# RX.net
KiCad netlist of a schematic drawn in Altium Designer
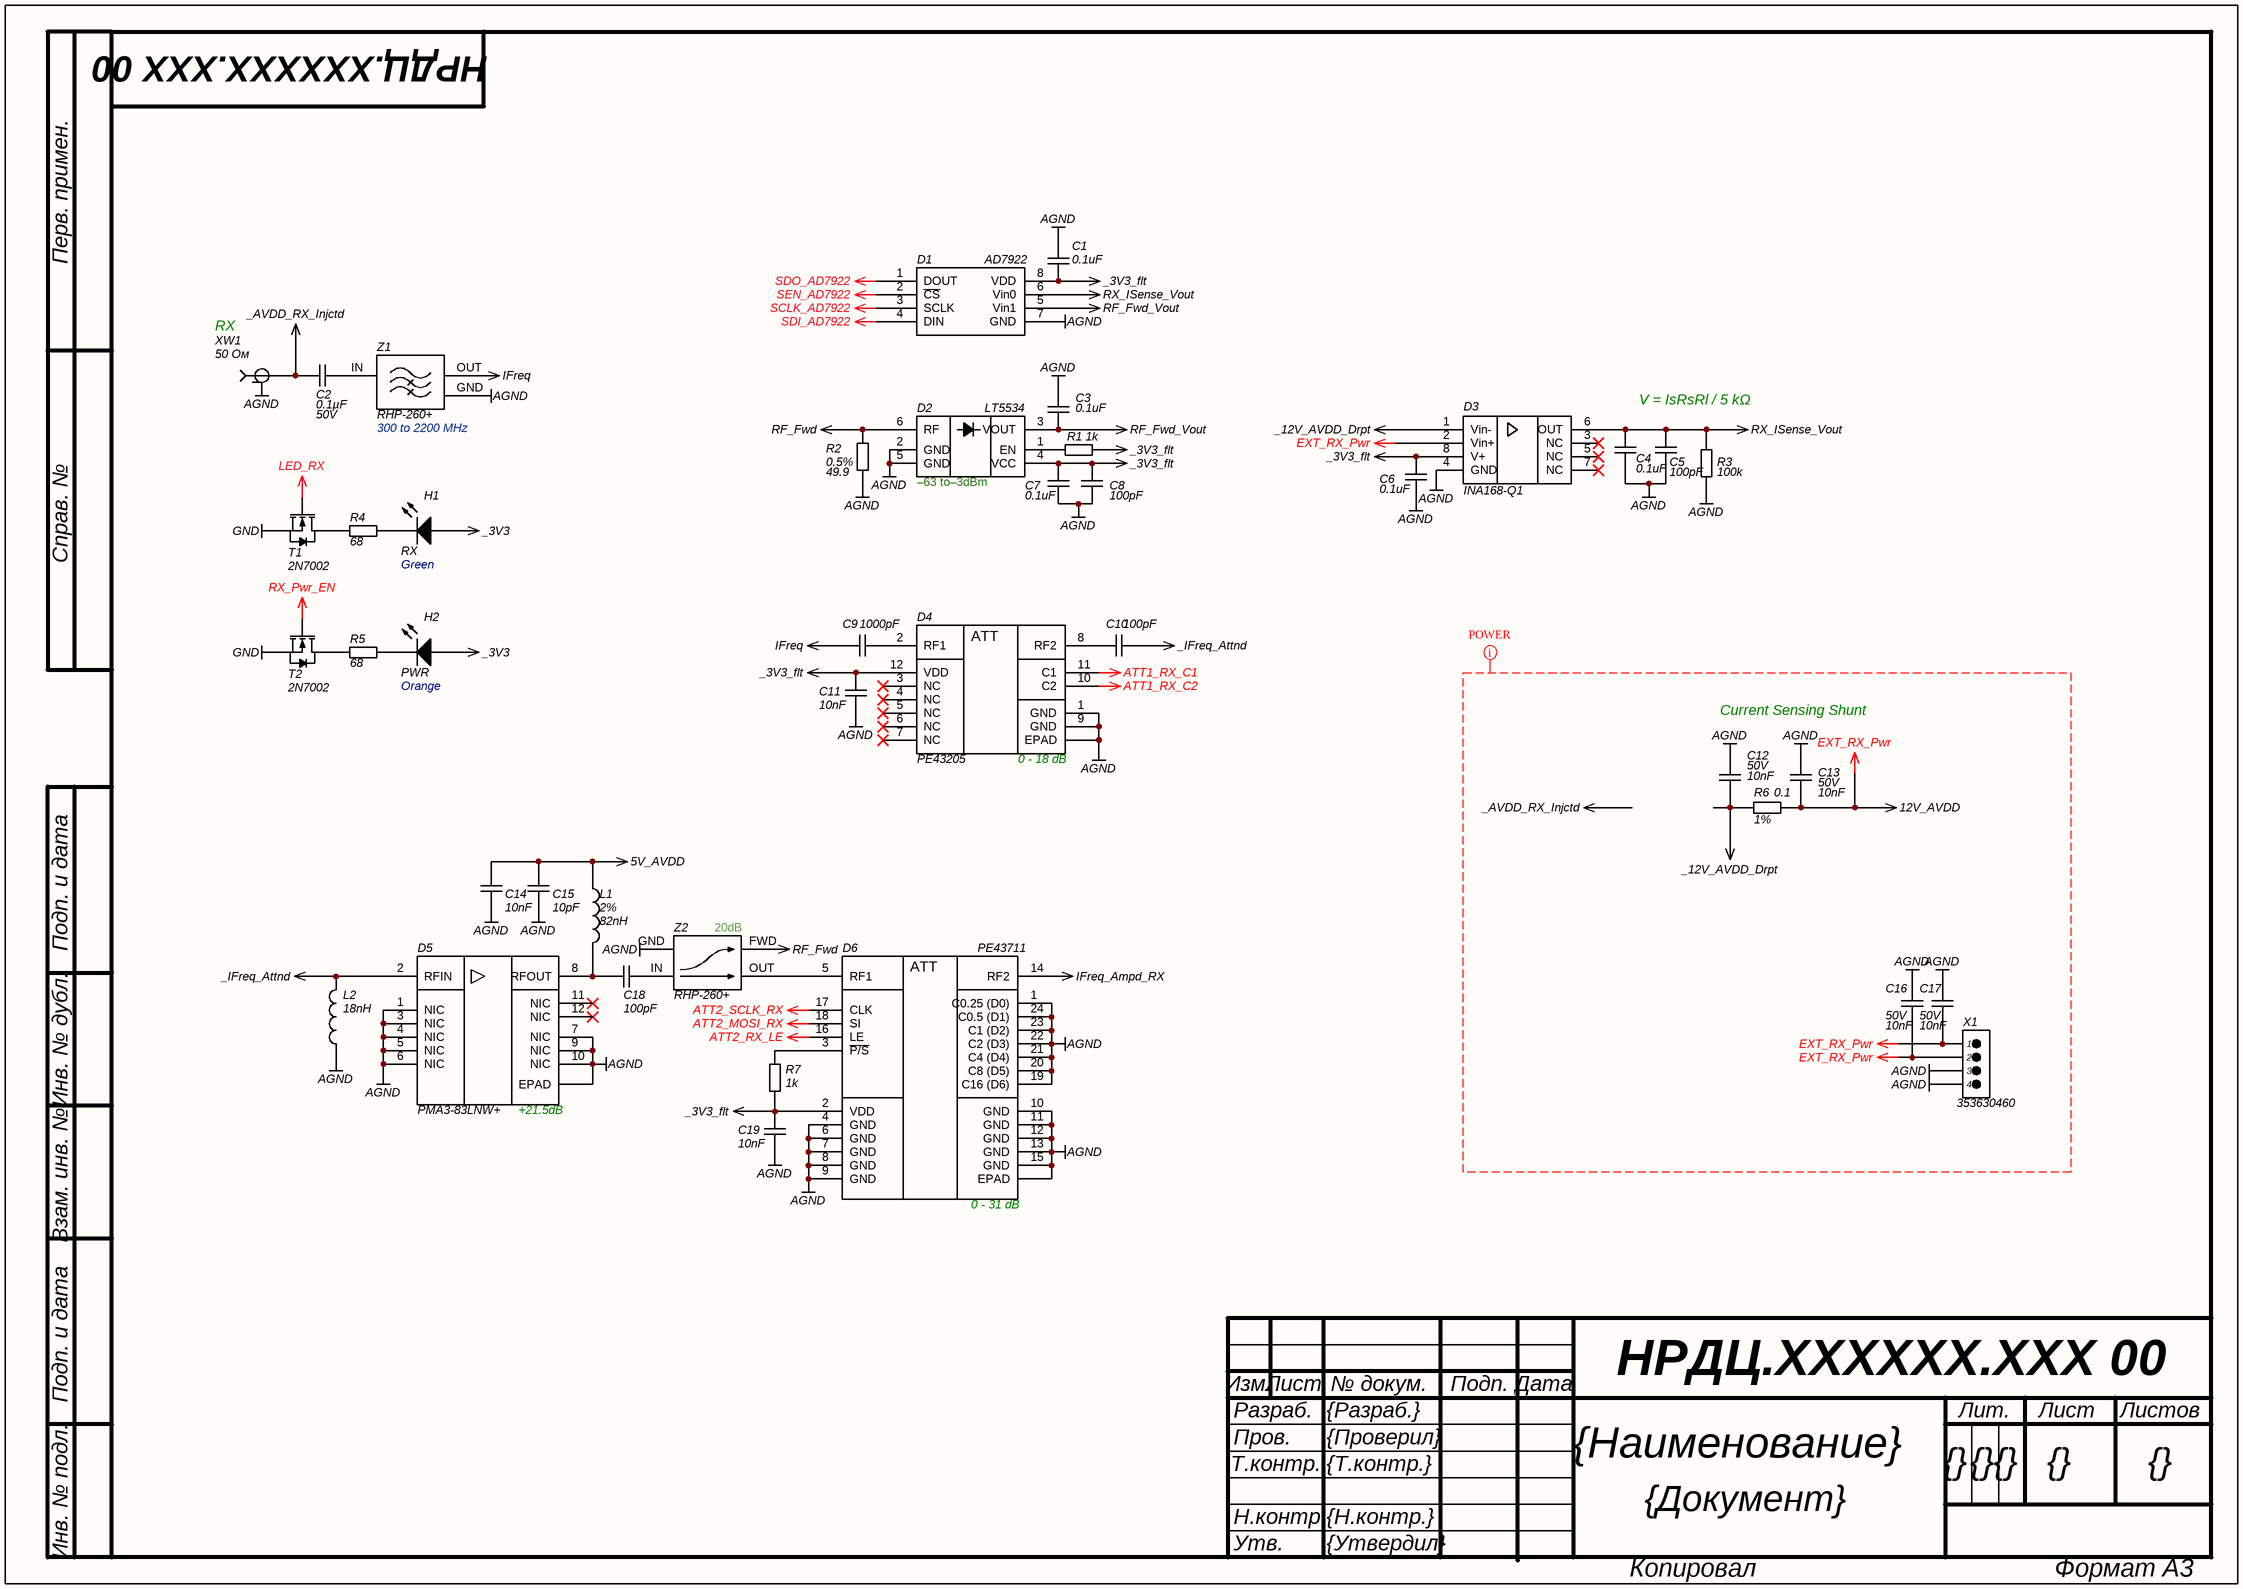
[diagram p0: RX.SchDoc]

(export (version "E")
  (design (tool "Eeschema 10.0.6"))
  (components
    (comp (ref "C1")
      (value "0.1uF")
      (footprint "C0402")
      (description "SMD Capacitor")
      (fields (field (name "MANUFACTURER") "Murata") (field (name "TOLERANCE") "10%"))
      (libsource (lib "Kintex_SDR") (part "CAP"))
    )
    (comp (ref "C2")
      (value "0.1µF")
      (footprint "C1206")
      (description "SMD Capacitor")
      (fields
        (field (name "MANUFACTURER") "Murata")
        (field (name "TOLERANCE") "5%")
        (field (name "VOLTAGE") "50V")
      )
      (libsource (lib "Kintex_SDR") (part "CAP"))
    )
    (comp (ref "C3")
      (value "0.1uF")
      (footprint "C0402")
      (description "SMD Capacitor")
      (fields (field (name "MANUFACTURER") "Murata") (field (name "TOLERANCE") "10%"))
      (libsource (lib "Kintex_SDR") (part "CAP"))
    )
    (comp (ref "C4")
      (value "0.1uF")
      (footprint "C0402")
      (description "SMD Capacitor")
      (fields (field (name "MANUFACTURER") "Murata") (field (name "TOLERANCE") "10%"))
      (libsource (lib "Kintex_SDR") (part "CAP"))
    )
    (comp (ref "C5")
      (value "100pF")
      (footprint "C0402")
      (description "SMD Capacitor")
      (fields (field (name "MANUFACTURER") "Murata") (field (name "TOLERANCE") "1%"))
      (libsource (lib "Kintex_SDR") (part "CAP"))
    )
    (comp (ref "C6")
      (value "0.1uF")
      (footprint "C0402")
      (description "SMD Capacitor")
      (fields (field (name "MANUFACTURER") "Murata") (field (name "TOLERANCE") "10%"))
      (libsource (lib "Kintex_SDR") (part "CAP"))
    )
    (comp (ref "C7")
      (value "0.1uF")
      (footprint "C0402")
      (description "SMD Capacitor")
      (fields (field (name "MANUFACTURER") "Murata") (field (name "TOLERANCE") "10%"))
      (libsource (lib "Kintex_SDR") (part "CAP"))
    )
    (comp (ref "C8")
      (value "100pF")
      (footprint "C0402")
      (description "SMD Capacitor")
      (fields (field (name "MANUFACTURER") "Murata") (field (name "TOLERANCE") "1%"))
      (libsource (lib "Kintex_SDR") (part "CAP"))
    )
    (comp (ref "C9")
      (value "1000pF")
      (footprint "C0402")
      (description "SMD Capacitor")
      (fields (field (name "MANUFACTURER") "Murata") (field (name "TOLERANCE") "5%"))
      (libsource (lib "Kintex_SDR") (part "CAP"))
    )
    (comp (ref "C10")
      (value "100pF")
      (footprint "C0402")
      (description "SMD Capacitor")
      (fields (field (name "MANUFACTURER") "Murata") (field (name "TOLERANCE") "1%"))
      (libsource (lib "Kintex_SDR") (part "CAP"))
    )
    (comp (ref "C11")
      (value "10nF")
      (footprint "C0402")
      (description "SMD Capacitor")
      (fields (field (name "MANUFACTURER") "Murata") (field (name "TOLERANCE") "10%"))
      (libsource (lib "Kintex_SDR") (part "CAP"))
    )
    (comp (ref "C12")
      (value "10nF")
      (footprint "C0402")
      (description "SMD Capacitor")
      (fields
        (field (name "MANUFACTURER") "Murata")
        (field (name "TOLERANCE") "5%")
        (field (name "VOLTAGE") "50V")
      )
      (libsource (lib "Kintex_SDR") (part "CAP"))
    )
    (comp (ref "C13")
      (value "10nF")
      (footprint "C0402")
      (description "SMD Capacitor")
      (fields
        (field (name "MANUFACTURER") "Murata")
        (field (name "TOLERANCE") "5%")
        (field (name "VOLTAGE") "50V")
      )
      (libsource (lib "Kintex_SDR") (part "CAP"))
    )
    (comp (ref "C14")
      (value "10nF")
      (footprint "C0402")
      (description "SMD Capacitor")
      (fields (field (name "MANUFACTURER") "Murata") (field (name "TOLERANCE") "10%"))
      (libsource (lib "Kintex_SDR") (part "CAP"))
    )
    (comp (ref "C15")
      (value "10pF")
      (footprint "C0402")
      (description "SMD Capacitor")
      (fields (field (name "MANUFACTURER") "Murata") (field (name "TOLERANCE") "1%"))
      (libsource (lib "Kintex_SDR") (part "CAP"))
    )
    (comp (ref "C16")
      (value "10nF")
      (footprint "C0402")
      (description "SMD Capacitor")
      (fields
        (field (name "MANUFACTURER") "Murata")
        (field (name "TOLERANCE") "5%")
        (field (name "VOLTAGE") "50V")
      )
      (libsource (lib "Kintex_SDR") (part "CAP"))
    )
    (comp (ref "C17")
      (value "10nF")
      (footprint "C0402")
      (description "SMD Capacitor")
      (fields
        (field (name "MANUFACTURER") "Murata")
        (field (name "TOLERANCE") "5%")
        (field (name "VOLTAGE") "50V")
      )
      (libsource (lib "Kintex_SDR") (part "CAP"))
    )
    (comp (ref "C18")
      (value "100pF")
      (footprint "C0402")
      (description "SMD Capacitor")
      (fields (field (name "MANUFACTURER") "Murata") (field (name "TOLERANCE") "1%"))
      (libsource (lib "Kintex_SDR") (part "CAP"))
    )
    (comp (ref "C19")
      (value "10nF")
      (footprint "C0402")
      (description "SMD Capacitor")
      (fields (field (name "MANUFACTURER") "Murata") (field (name "TOLERANCE") "10%"))
      (libsource (lib "Kintex_SDR") (part "CAP"))
    )
    (comp (ref "D1")
      (value "AD7922")
      (footprint "MSOP-8")
      (description "1 MSPS, 10-/12-Bit ADC")
      (fields (field (name "MANUFACTURER") "Analog Device") (field (name "VOLTAGE") "2.35 V to 5.25 V"))
      (libsource (lib "Kintex_SDR") (part "AD79x2"))
    )
    (comp (ref "D2")
      (value "LT5534")
      (footprint "DBLib:SC70")
      (description "50MHz to 3GHz monolithic RF power\r\ndetector")
      (fields
        (field (name "MANUFACTURER") "Linear Technology")
        (field (name "VOLTAGE") "Single 2.7V to 5.25V")
        (field (name "RF INPUT POWER RANGE") "–63 to–3dBm")
      )
      (libsource (lib "DBLib") (part "LT5534"))
    )
    (comp (ref "D3")
      (value "INA168-Q1")
      (footprint "DBLib:TSSOP (8)")
      (description "Automotive-Grade, High-Side, Current-Output, Current-Shunt Monitor")
      (fields (field (name "MANUFACTURER") "Texas Instruments") (field (name "VOLTAGE") "2.7 V to 60 V"))
      (libsource (lib "DBLib") (part "INA168-Q1"))
    )
    (comp (ref "D4")
      (value "PE43205")
      (footprint "DBLib:QFN-12")
      (description "50Ω, HaRP™ technology-enhanced\r\nfast switching 2-bit RF Digital Step Attenuator")
      (fields (field (name "MANUFACTURER") "Peregrine Technical Solutions"))
      (libsource (lib "DBLib") (part "PE43205"))
    )
    (comp (ref "D5")
      (value "PMA3-83LNW+")
      (footprint "DQ1225")
      (description "PHEMT based wideband, low noise MMIC amplifier")
      (fields (field (name "MANUFACTURER") "Mini-Circuits"))
      (libsource (lib "DBLib") (part "PMA3-83LNW+"))
    )
    (comp (ref "D6")
      (value "PE43711")
      (footprint "QFN-24")
      (description "The PE43711 is a 50Ω, HaRP™ technology-enhanced, 7-bit RF digital step attenuator")
      (fields (field (name "MANUFACTURER") "Peregrine Technical Solutions"))
      (libsource (lib "DBLib") (part "PE43711"))
    )
    (comp (ref "H1")
      (value "RX")
      (footprint "LED")
      (description "CHIP LED LAMP")
      (fields (field (name "MANUFACTURER") "Kingbright") (field (name "COLOR") "Green"))
      (libsource (lib "DBLib") (part "LED"))
    )
    (comp (ref "H2")
      (value "PWR")
      (footprint "LED")
      (description "CHIP LED LAMP")
      (fields (field (name "MANUFACTURER") "Kingbright") (field (name "COLOR") "Orange"))
      (libsource (lib "DBLib") (part "LED"))
    )
    (comp (ref "L1")
      (value "82nH")
      (footprint "DBLib:L0603_HP")
      (description "Chip SMD Inductor")
      (fields
        (field (name "MANUFACTURER") "Coilcraft")
        (field (name "TOLERANCE") "2%")
        (field (name "Comment") "Inductor RF")
      )
      (libsource (lib "DBLib") (part "Inductor RF"))
    )
    (comp (ref "L2")
      (value "18nH")
      (footprint "DBLib:L0603_HP")
      (description "Chip SMD Inductor")
      (fields (field (name "MANUFACTURER") "Coilcraft") (field (name "TOLERANCE") "5%"))
      (libsource (lib "") (part "Inductor RF_1"))
    )
    (comp (ref "R1")
      (value "1k")
      (footprint "R0402")
      (description "SMD Resistor")
      (fields (field (name "POWER") "0.062 Wt") (field (name "TOLERANCE") "5%"))
      (libsource (lib "Kintex_SDR") (part "RES"))
    )
    (comp (ref "R2")
      (value "49.9")
      (footprint "R0402")
      (description "SMD Resistor")
      (fields
        (field (name "POWER") "0.063 Wt")
        (field (name "TOLERANCE") "0.5%")
        (field (name "MANUFACTURER") "Panasonic Electronic Components")
      )
      (libsource (lib "") (part "RES_1"))
    )
    (comp (ref "R3")
      (value "100k")
      (footprint "R0402")
      (description "SMD Resistor")
      (fields (field (name "POWER") "1/5 Wt") (field (name "TOLERANCE") "1%"))
      (libsource (lib "") (part "RES_3"))
    )
    (comp (ref "R4")
      (value "68")
      (footprint "R0402")
      (description "SMD Resistor")
      (fields (field (name "POWER") "0.062 Wt") (field (name "TOLERANCE") "5%"))
      (libsource (lib "") (part "RES_2"))
    )
    (comp (ref "R5")
      (value "68")
      (footprint "R0402")
      (description "SMD Resistor")
      (fields (field (name "POWER") "0.062 Wt") (field (name "TOLERANCE") "5%"))
      (libsource (lib "Kintex_SDR") (part "RES"))
    )
    (comp (ref "R6")
      (value "0.1")
      (footprint "R0805")
      (description "SMD Resistor")
      (fields
        (field (name "POWER") "1/2 Wt")
        (field (name "TOLERANCE") "1%")
        (field (name "MANUFACTURER") "Panasonic Electronic Components")
      )
      (libsource (lib "Kintex_SDR") (part "RES"))
    )
    (comp (ref "R7")
      (value "1k")
      (footprint "R0402")
      (description "SMD Resistor")
      (fields (field (name "POWER") "0.062 Wt") (field (name "TOLERANCE") "5%"))
      (libsource (lib "") (part "RES_3"))
    )
    (comp (ref "T1")
      (value "2N7002")
      (footprint "SOT-23")
      (description "N-Channel MOSFET 2N7002")
      (fields (field (name "VOLTAGE") "60V"))
      (libsource (lib "Kintex_SDR") (part "2N7002"))
    )
    (comp (ref "T2")
      (value "2N7002")
      (footprint "SOT-23")
      (description "N-Channel MOSFET 2N7002")
      (fields (field (name "VOLTAGE") "60V"))
      (libsource (lib "Kintex_SDR") (part "2N7002"))
    )
    (comp (ref "X1")
      (value "353630460")
      (footprint "DBLib:CON_353630460")
      (description "2.00mm Pitch Sherlock Wire-to-Board Header, Right-Angle, with Positive Lock, 4 Circuits")
      (fields (field (name "MANUFACTURER") "Molex"))
      (libsource (lib "DBLib") (part "353630460"))
    )
    (comp (ref "XW1")
      (value "50 Ом")
      (footprint "MOLEX SD-73251-135 (Gold)")
      (description "50 Ohms, SMA Jack, Vertica")
      (fields (field (name "MANUFACTURER") "Molex"))
      (libsource (lib "DBLib") (part "RF Connector"))
    )
    (comp (ref "Z1")
      (value "RHP-260+")
      (footprint "GP731")
      (description "High Pass Filter")
      (fields (field (name "MANUFACTURER") "Mini-Circuits") (field (name "FREQUENCY") "300 to 2200 MHz"))
      (libsource (lib "DBLib") (part "RHP-260+"))
    )
    (comp (ref "Z2")
      (value "RHP-260+")
      (footprint "DBLib:AH202")
      (description "Directional Coupler")
      (fields (field (name "MANUFACTURER") "Mini-Circuits") (field (name "COUPLING") "20dB"))
      (libsource (lib "DBLib") (part "SYD-20-33+"))
    )
  )
  (nets
    (net (code "1") (name "5V_AVDD") (class "Default")
      (node (ref "C14") (pin "2") (pinfunction "2_2") (pintype "passive"))
      (node (ref "C15") (pin "2") (pinfunction "2_2") (pintype "passive"))
      (node (ref "L1") (pin "2") (pinfunction "2_2") (pintype "passive"))
    )
    (net (code "2") (name "12V_AVDD") (class "Default")
      (node (ref "C13") (pin "1") (pinfunction "1_1") (pintype "passive"))
      (node (ref "C16") (pin "2") (pinfunction "2_2") (pintype "passive"))
      (node (ref "C17") (pin "2") (pinfunction "2_2") (pintype "passive"))
      (node (ref "D3") (pin "2") (pinfunction "Vin+_2") (pintype "passive"))
      (node (ref "R6") (pin "1") (pinfunction "1_1") (pintype "passive"))
      (node (ref "X1") (pin "1") (pinfunction "1_1") (pintype "passive"))
      (node (ref "X1") (pin "2") (pinfunction "2_2") (pintype "passive"))
    )
    (net (code "3") (name "AGND") (class "Default")
      (node (ref "C1") (pin "2") (pinfunction "2_2") (pintype "passive"))
      (node (ref "C11") (pin "1") (pinfunction "1_1") (pintype "passive"))
      (node (ref "C12") (pin "2") (pinfunction "2_2") (pintype "passive"))
      (node (ref "C13") (pin "2") (pinfunction "2_2") (pintype "passive"))
      (node (ref "C14") (pin "1") (pinfunction "1_1") (pintype "passive"))
      (node (ref "C15") (pin "1") (pinfunction "1_1") (pintype "passive"))
      (node (ref "C16") (pin "1") (pinfunction "1_1") (pintype "passive"))
      (node (ref "C17") (pin "1") (pinfunction "1_1") (pintype "passive"))
      (node (ref "C19") (pin "1") (pinfunction "1_1") (pintype "passive"))
      (node (ref "C3") (pin "1") (pinfunction "1_1") (pintype "passive"))
      (node (ref "C4") (pin "1") (pinfunction "1_1") (pintype "passive"))
      (node (ref "C5") (pin "1") (pinfunction "1_1") (pintype "passive"))
      (node (ref "C6") (pin "1") (pinfunction "1_1") (pintype "passive"))
      (node (ref "C7") (pin "1") (pinfunction "1_1") (pintype "passive"))
      (node (ref "C8") (pin "1") (pinfunction "1_1") (pintype "passive"))
      (node (ref "D1") (pin "7") (pinfunction "GND_7") (pintype "passive"))
      (node (ref "D2") (pin "2") (pinfunction "GND_2") (pintype "passive"))
      (node (ref "D2") (pin "5") (pinfunction "GND_5") (pintype "passive"))
      (node (ref "D3") (pin "4") (pinfunction "GND_4") (pintype "passive"))
      (node (ref "D4") (pin "1") (pinfunction "GND_1") (pintype "passive"))
      (node (ref "D4") (pin "13") (pinfunction "EPAD_13") (pintype "passive"))
      (node (ref "D4") (pin "9") (pinfunction "GND_9") (pintype "passive"))
      (node (ref "D5") (pin "1") (pinfunction "NIC_1") (pintype "passive"))
      (node (ref "D5") (pin "10") (pinfunction "NIC_10") (pintype "passive"))
      (node (ref "D5") (pin "13") (pinfunction "EPAD_13") (pintype "passive"))
      (node (ref "D5") (pin "3") (pinfunction "NIC_3") (pintype "passive"))
      (node (ref "D5") (pin "4") (pinfunction "NIC_4") (pintype "passive"))
      (node (ref "D5") (pin "5") (pinfunction "NIC_5") (pintype "passive"))
      (node (ref "D5") (pin "6") (pinfunction "NIC_6") (pintype "passive"))
      (node (ref "D5") (pin "7") (pinfunction "NIC_7") (pintype "passive"))
      (node (ref "D5") (pin "9") (pinfunction "NIC_9") (pintype "passive"))
      (node (ref "D6") (pin "1") (pinfunction "C0.25_(D0)_1") (pintype "passive"))
      (node (ref "D6") (pin "10") (pinfunction "GND_10") (pintype "passive"))
      (node (ref "D6") (pin "11") (pinfunction "GND_11") (pintype "passive"))
      (node (ref "D6") (pin "12") (pinfunction "GND_12") (pintype "passive"))
      (node (ref "D6") (pin "13") (pinfunction "GND_13") (pintype "passive"))
      (node (ref "D6") (pin "15") (pinfunction "GND_15") (pintype "passive"))
      (node (ref "D6") (pin "19") (pinfunction "C16_(D6)_19") (pintype "passive"))
      (node (ref "D6") (pin "20") (pinfunction "C8_(D5)_20") (pintype "passive"))
      (node (ref "D6") (pin "21") (pinfunction "C4_(D4)_21") (pintype "passive"))
      (node (ref "D6") (pin "22") (pinfunction "C2_(D3)_22") (pintype "passive"))
      (node (ref "D6") (pin "23") (pinfunction "C1_(D2)_23") (pintype "passive"))
      (node (ref "D6") (pin "24") (pinfunction "C0.5_(D1)_24") (pintype "passive"))
      (node (ref "D6") (pin "25") (pinfunction "EPAD_25") (pintype "passive"))
      (node (ref "D6") (pin "4") (pinfunction "GND_4") (pintype "passive"))
      (node (ref "D6") (pin "6") (pinfunction "GND_6") (pintype "passive"))
      (node (ref "D6") (pin "7") (pinfunction "GND_7") (pintype "passive"))
      (node (ref "D6") (pin "8") (pinfunction "GND_8") (pintype "passive"))
      (node (ref "D6") (pin "9") (pinfunction "GND_9") (pintype "passive"))
      (node (ref "L2") (pin "1") (pinfunction "1_1") (pintype "passive"))
      (node (ref "R2") (pin "2") (pinfunction "2_2") (pintype "passive"))
      (node (ref "R3") (pin "1") (pinfunction "1_1") (pintype "passive"))
      (node (ref "X1") (pin "3") (pinfunction "3_3") (pintype "passive"))
      (node (ref "X1") (pin "4") (pinfunction "4_4") (pintype "passive"))
      (node (ref "XW1") (pin "G") (pinfunction "GND_G") (pintype "passive"))
      (node (ref "Z1") (pin "GND") (pinfunction "GND_GND") (pintype "passive"))
    )
    (net (code "4") (name "ATT1_RX_C1") (class "Default")
      (node (ref "D4") (pin "11") (pinfunction "C1_11") (pintype "passive"))
    )
    (net (code "5") (name "ATT1_RX_C2") (class "Default")
      (node (ref "D4") (pin "10") (pinfunction "C2_10") (pintype "passive"))
    )
    (net (code "6") (name "ATT2_MOSI_RX") (class "Default")
      (node (ref "D6") (pin "18") (pinfunction "SI_18") (pintype "passive"))
    )
    (net (code "7") (name "ATT2_RX_LE") (class "Default")
      (node (ref "D6") (pin "16") (pinfunction "LE_16") (pintype "passive"))
    )
    (net (code "8") (name "ATT2_SCLK_RX") (class "Default")
      (node (ref "D6") (pin "17") (pinfunction "CLK_17") (pintype "passive"))
    )
    (net (code "9") (name "GND") (class "Default")
      (node (ref "T1") (pin "2") (pinfunction "S_2") (pintype "passive"))
      (node (ref "T2") (pin "2") (pinfunction "S_2") (pintype "passive"))
    )
    (net (code "10") (name "IFreq") (class "Default")
      (node (ref "C9") (pin "1") (pinfunction "1_1") (pintype "passive"))
      (node (ref "Z1") (pin "OUT") (pinfunction "OUT_OUT") (pintype "passive"))
    )
    (net (code "11") (name "IFreq_Ampd_RX") (class "Default")
      (node (ref "D6") (pin "14") (pinfunction "RF2_14") (pintype "passive"))
    )
    (net (code "12") (name "LED_RX") (class "Default")
      (node (ref "T1") (pin "1") (pinfunction "G_1") (pintype "passive"))
    )
    (net (code "13") (name "Net-(C2-Pad2)") (class "Default")
      (node (ref "C2") (pin "2") (pinfunction "2_2") (pintype "passive"))
      (node (ref "Z1") (pin "IN") (pinfunction "IN_IN") (pintype "passive"))
    )
    (net (code "14") (name "Net-(C18-Pad2)") (class "Default")
      (node (ref "C18") (pin "2") (pinfunction "2_2") (pintype "passive"))
      (node (ref "Z2") (pin "IN") (pinfunction "IN_IN") (pintype "passive"))
    )
    (net (code "15") (name "Net-(D2-EN)") (class "Default")
      (node (ref "D2") (pin "1") (pinfunction "EN_1") (pintype "passive"))
      (node (ref "R1") (pin "2") (pinfunction "2_2") (pintype "passive"))
    )
    (net (code "16") (name "Net-(D4-RF1)") (class "Default")
      (node (ref "C9") (pin "2") (pinfunction "2_2") (pintype "passive"))
      (node (ref "D4") (pin "2") (pinfunction "RF1_2") (pintype "passive"))
    )
    (net (code "17") (name "Net-(D4-RF2)") (class "Default")
      (node (ref "C10") (pin "1") (pinfunction "1_1") (pintype "passive"))
      (node (ref "D4") (pin "8") (pinfunction "RF2_8") (pintype "passive"))
    )
    (net (code "18") (name "Net-(D5-RFOUT)") (class "Default")
      (node (ref "C18") (pin "1") (pinfunction "1_1") (pintype "passive"))
      (node (ref "D5") (pin "8") (pinfunction "RFOUT_8") (pintype "passive"))
      (node (ref "L1") (pin "1") (pinfunction "1_1") (pintype "passive"))
    )
    (net (code "19") (name "Net-(D6-RF1)") (class "Default")
      (node (ref "D6") (pin "5") (pinfunction "RF1_5") (pintype "passive"))
      (node (ref "Z2") (pin "OUT") (pinfunction "OUT_OUT") (pintype "passive"))
    )
    (net (code "20") (name "Net-(D6-~{P{slash}S})") (class "Default")
      (node (ref "D6") (pin "3") (pinfunction "~{P/S}_3") (pintype "passive"))
      (node (ref "R7") (pin "2") (pinfunction "2_2") (pintype "passive"))
    )
    (net (code "21") (name "Net-(H1-K)") (class "Default")
      (node (ref "H1") (pin "1") (pinfunction "K_1") (pintype "passive"))
      (node (ref "R4") (pin "2") (pinfunction "2_2") (pintype "passive"))
    )
    (net (code "22") (name "Net-(H2-K)") (class "Default")
      (node (ref "H2") (pin "1") (pinfunction "K_1") (pintype "passive"))
      (node (ref "R5") (pin "1") (pinfunction "1_1") (pintype "passive"))
    )
    (net (code "23") (name "Net-(T1-D)") (class "Default")
      (node (ref "R4") (pin "1") (pinfunction "1_1") (pintype "passive"))
      (node (ref "T1") (pin "3") (pinfunction "D_3") (pintype "passive"))
    )
    (net (code "24") (name "Net-(T2-D)") (class "Default")
      (node (ref "R5") (pin "2") (pinfunction "2_2") (pintype "passive"))
      (node (ref "T2") (pin "3") (pinfunction "D_3") (pintype "passive"))
    )
    (net (code "25") (name "RF_Fwd") (class "Default")
      (node (ref "D2") (pin "6") (pinfunction "RF_6") (pintype "passive"))
      (node (ref "R2") (pin "1") (pinfunction "1_1") (pintype "passive"))
      (node (ref "Z2") (pin "FWD") (pinfunction "FWD_FWD") (pintype "passive"))
    )
    (net (code "26") (name "RF_Fwd_Vout") (class "Default")
      (node (ref "C3") (pin "2") (pinfunction "2_2") (pintype "passive"))
      (node (ref "D1") (pin "5") (pinfunction "Vin1_5") (pintype "passive"))
      (node (ref "D2") (pin "3") (pinfunction "VOUT_3") (pintype "passive"))
    )
    (net (code "27") (name "RX_ISense_Vout") (class "Default")
      (node (ref "C4") (pin "2") (pinfunction "2_2") (pintype "passive"))
      (node (ref "C5") (pin "2") (pinfunction "2_2") (pintype "passive"))
      (node (ref "D1") (pin "6") (pinfunction "Vin0_6") (pintype "passive"))
      (node (ref "D3") (pin "6") (pinfunction "OUT_6") (pintype "passive"))
      (node (ref "R3") (pin "2") (pinfunction "2_2") (pintype "passive"))
    )
    (net (code "28") (name "RX_Pwr_EN") (class "Default")
      (node (ref "T2") (pin "1") (pinfunction "G_1") (pintype "passive"))
    )
    (net (code "29") (name "SCLK_AD7922") (class "Default")
      (node (ref "D1") (pin "3") (pinfunction "SCLK_3") (pintype "passive"))
    )
    (net (code "30") (name "SDI_AD7922") (class "Default")
      (node (ref "D1") (pin "4") (pinfunction "DIN_4") (pintype "passive"))
    )
    (net (code "31") (name "SDO_AD7922") (class "Default")
      (node (ref "D1") (pin "1") (pinfunction "DOUT_1") (pintype "passive"))
    )
    (net (code "32") (name "SEN_AD7922") (class "Default")
      (node (ref "D1") (pin "2") (pinfunction "~{CS}_2") (pintype "passive"))
    )
    (net (code "33") (name "_3V3") (class "Default")
      (node (ref "H1") (pin "2") (pinfunction "A_2") (pintype "passive"))
      (node (ref "H2") (pin "2") (pinfunction "A_2") (pintype "passive"))
    )
    (net (code "34") (name "_3V3_flt") (class "Default")
      (node (ref "C1") (pin "1") (pinfunction "1_1") (pintype "passive"))
      (node (ref "C11") (pin "2") (pinfunction "2_2") (pintype "passive"))
      (node (ref "C19") (pin "2") (pinfunction "2_2") (pintype "passive"))
      (node (ref "C6") (pin "2") (pinfunction "2_2") (pintype "passive"))
      (node (ref "C7") (pin "2") (pinfunction "2_2") (pintype "passive"))
      (node (ref "C8") (pin "2") (pinfunction "2_2") (pintype "passive"))
      (node (ref "D1") (pin "8") (pinfunction "VDD_8") (pintype "passive"))
      (node (ref "D2") (pin "4") (pinfunction "VCC_4") (pintype "passive"))
      (node (ref "D3") (pin "8") (pinfunction "V+_8") (pintype "passive"))
      (node (ref "D4") (pin "12") (pinfunction "VDD_12") (pintype "passive"))
      (node (ref "D6") (pin "2") (pinfunction "VDD_2") (pintype "passive"))
      (node (ref "R1") (pin "1") (pinfunction "1_1") (pintype "passive"))
      (node (ref "R7") (pin "1") (pinfunction "1_1") (pintype "passive"))
    )
    (net (code "35") (name "_12V_AVDD_Drpt") (class "Default")
      (node (ref "C12") (pin "1") (pinfunction "1_1") (pintype "passive"))
      (node (ref "D3") (pin "1") (pinfunction "Vin-_1") (pintype "passive"))
      (node (ref "R6") (pin "2") (pinfunction "2_2") (pintype "passive"))
    )
    (net (code "36") (name "_AVDD_RX_Injctd") (class "Default")
      (node (ref "C2") (pin "1") (pinfunction "1_1") (pintype "passive"))
      (node (ref "XW1") (pin "S") (pinfunction "RF_S") (pintype "passive"))
    )
    (net (code "37") (name "_IFreq_Attnd") (class "Default")
      (node (ref "C10") (pin "2") (pinfunction "2_2") (pintype "passive"))
      (node (ref "D5") (pin "2") (pinfunction "RFIN_2") (pintype "passive"))
      (node (ref "L2") (pin "2") (pinfunction "2_2") (pintype "passive"))
    )
    (net (code "38") (name "unconnected-(D3-NC-Pad3)") (class "Default")
      (node (ref "D3") (pin "3") (pinfunction "NC_3") (pintype "passive+no_connect"))
    )
    (net (code "39") (name "unconnected-(D3-NC-Pad5)") (class "Default")
      (node (ref "D3") (pin "5") (pinfunction "NC_5") (pintype "passive+no_connect"))
    )
    (net (code "40") (name "unconnected-(D3-NC-Pad7)") (class "Default")
      (node (ref "D3") (pin "7") (pinfunction "NC_7") (pintype "passive+no_connect"))
    )
    (net (code "41") (name "unconnected-(D4-NC-Pad3)") (class "Default")
      (node (ref "D4") (pin "3") (pinfunction "NC_3") (pintype "passive+no_connect"))
    )
    (net (code "42") (name "unconnected-(D4-NC-Pad4)") (class "Default")
      (node (ref "D4") (pin "4") (pinfunction "NC_4") (pintype "passive+no_connect"))
    )
    (net (code "43") (name "unconnected-(D4-NC-Pad5)") (class "Default")
      (node (ref "D4") (pin "5") (pinfunction "NC_5") (pintype "passive+no_connect"))
    )
    (net (code "44") (name "unconnected-(D4-NC-Pad6)") (class "Default")
      (node (ref "D4") (pin "6") (pinfunction "NC_6") (pintype "passive+no_connect"))
    )
    (net (code "45") (name "unconnected-(D4-NC-Pad7)") (class "Default")
      (node (ref "D4") (pin "7") (pinfunction "NC_7") (pintype "passive+no_connect"))
    )
    (net (code "46") (name "unconnected-(D5-NIC-Pad11)") (class "Default")
      (node (ref "D5") (pin "11") (pinfunction "NIC_11") (pintype "passive+no_connect"))
    )
    (net (code "47") (name "unconnected-(D5-NIC-Pad12)") (class "Default")
      (node (ref "D5") (pin "12") (pinfunction "NIC_12") (pintype "passive+no_connect"))
    )
    (net (code "48") (name "unconnected-(Z2-PadGND)") (class "Default")
      (node (ref "Z2") (pin "GND") (pinfunction "GND_GND") (pintype "passive"))
    )
  )
)
